# di_box.net
KiCad netlist of a schematic drawn in EAGLE
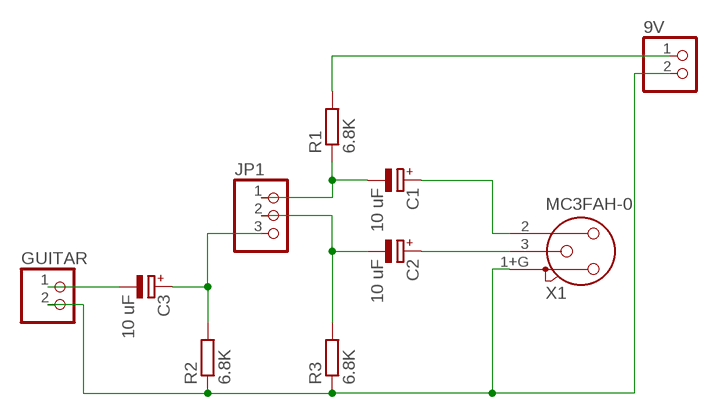
[diagram p0: schematic, sheet 1]

(export (version "E")
  (design (tool "Eeschema 10.0.6"))
  (components
    (comp (ref "9V")
      (value "PINHD-1X2")
      (footprint "eagle-import:1X02")
      (libsource (lib "eagle-import") (part "PINHD-1X2"))
    )
    (comp (ref "C1")
      (value "10 uF")
      (footprint "eagle-import:E2-4")
      (libsource (lib "eagle-import") (part "CPOL-EUE2-4"))
    )
    (comp (ref "C2")
      (value "10 uF")
      (footprint "eagle-import:E2-4")
      (libsource (lib "eagle-import") (part "CPOL-EUE2-4"))
    )
    (comp (ref "C3")
      (value "10 uF")
      (footprint "eagle-import:E2-4")
      (libsource (lib "eagle-import") (part "CPOL-EUE2-4"))
    )
    (comp (ref "GUITAR")
      (value "PINHD-1X2")
      (footprint "eagle-import:1X02")
      (libsource (lib "eagle-import") (part "PINHD-1X2"))
    )
    (comp (ref "JP1")
      (value "PINHD-1X3")
      (footprint "eagle-import:1X03")
      (libsource (lib "eagle-import") (part "PINHD-1X3"))
    )
    (comp (ref "R1")
      (value "6.8K")
      (footprint "eagle-import:0207_10")
      (libsource (lib "eagle-import") (part "R-EU_0207/10"))
    )
    (comp (ref "R2")
      (value "6.8K")
      (footprint "eagle-import:0207_10")
      (libsource (lib "eagle-import") (part "R-EU_0207/10"))
    )
    (comp (ref "R3")
      (value "6.8K")
      (footprint "eagle-import:0207_10")
      (libsource (lib "eagle-import") (part "R-EU_0207/10"))
    )
    (comp (ref "X1")
      (value "MC3FAH-0")
      (footprint "eagle-import:NC3FAH1-0")
      (libsource (lib "eagle-import") (part "MC3?FAH-0"))
    )
  )
  (nets
    (net (code "1") (name "Net-(9V-Pad1)") (class "Default")
      (node (ref "9V") (pin "1") (pinfunction "1_1") (pintype "passive"))
      (node (ref "R1") (pin "2") (pinfunction "2_2") (pintype "passive"))
    )
    (net (code "2") (name "Net-(C1-Pad+)") (class "Default")
      (node (ref "C1") (pin "+") (pinfunction "+_+") (pintype "passive"))
      (node (ref "X1") (pin "2") (pinfunction "2_2") (pintype "passive"))
    )
    (net (code "3") (name "Net-(C1-Pad-)") (class "Default")
      (node (ref "C1") (pin "-") (pinfunction "-_-") (pintype "passive"))
      (node (ref "JP1") (pin "1") (pinfunction "1_1") (pintype "passive"))
      (node (ref "R1") (pin "1") (pinfunction "1_1") (pintype "passive"))
    )
    (net (code "4") (name "Net-(C2-Pad+)") (class "Default")
      (node (ref "C2") (pin "+") (pinfunction "+_+") (pintype "passive"))
      (node (ref "X1") (pin "3") (pinfunction "3_3") (pintype "passive"))
    )
    (net (code "5") (name "Net-(C2-Pad-)") (class "Default")
      (node (ref "C2") (pin "-") (pinfunction "-_-") (pintype "passive"))
      (node (ref "JP1") (pin "2") (pinfunction "2_2") (pintype "passive"))
      (node (ref "R3") (pin "2") (pinfunction "2_2") (pintype "passive"))
    )
    (net (code "6") (name "Net-(C3-Pad+)") (class "Default")
      (node (ref "C3") (pin "+") (pinfunction "+_+") (pintype "passive"))
      (node (ref "JP1") (pin "3") (pinfunction "3_3") (pintype "passive"))
      (node (ref "R2") (pin "2") (pinfunction "2_2") (pintype "passive"))
    )
    (net (code "7") (name "Net-(C3-Pad-)") (class "Default")
      (node (ref "C3") (pin "-") (pinfunction "-_-") (pintype "passive"))
      (node (ref "GUITAR") (pin "1") (pinfunction "1_1") (pintype "passive"))
    )
    (net (code "8") (name "Net-(X1-1)") (class "Default")
      (node (ref "9V") (pin "2") (pinfunction "2_2") (pintype "passive"))
      (node (ref "GUITAR") (pin "2") (pinfunction "2_2") (pintype "passive"))
      (node (ref "R2") (pin "1") (pinfunction "1_1") (pintype "passive"))
      (node (ref "R3") (pin "1") (pinfunction "1_1") (pintype "passive"))
      (node (ref "X1") (pin "1+G") (pinfunction "1_1+G") (pintype "passive"))
    )
  )
)
